# BUTTONS.net
KiCad netlist of a schematic drawn in Altium Designer
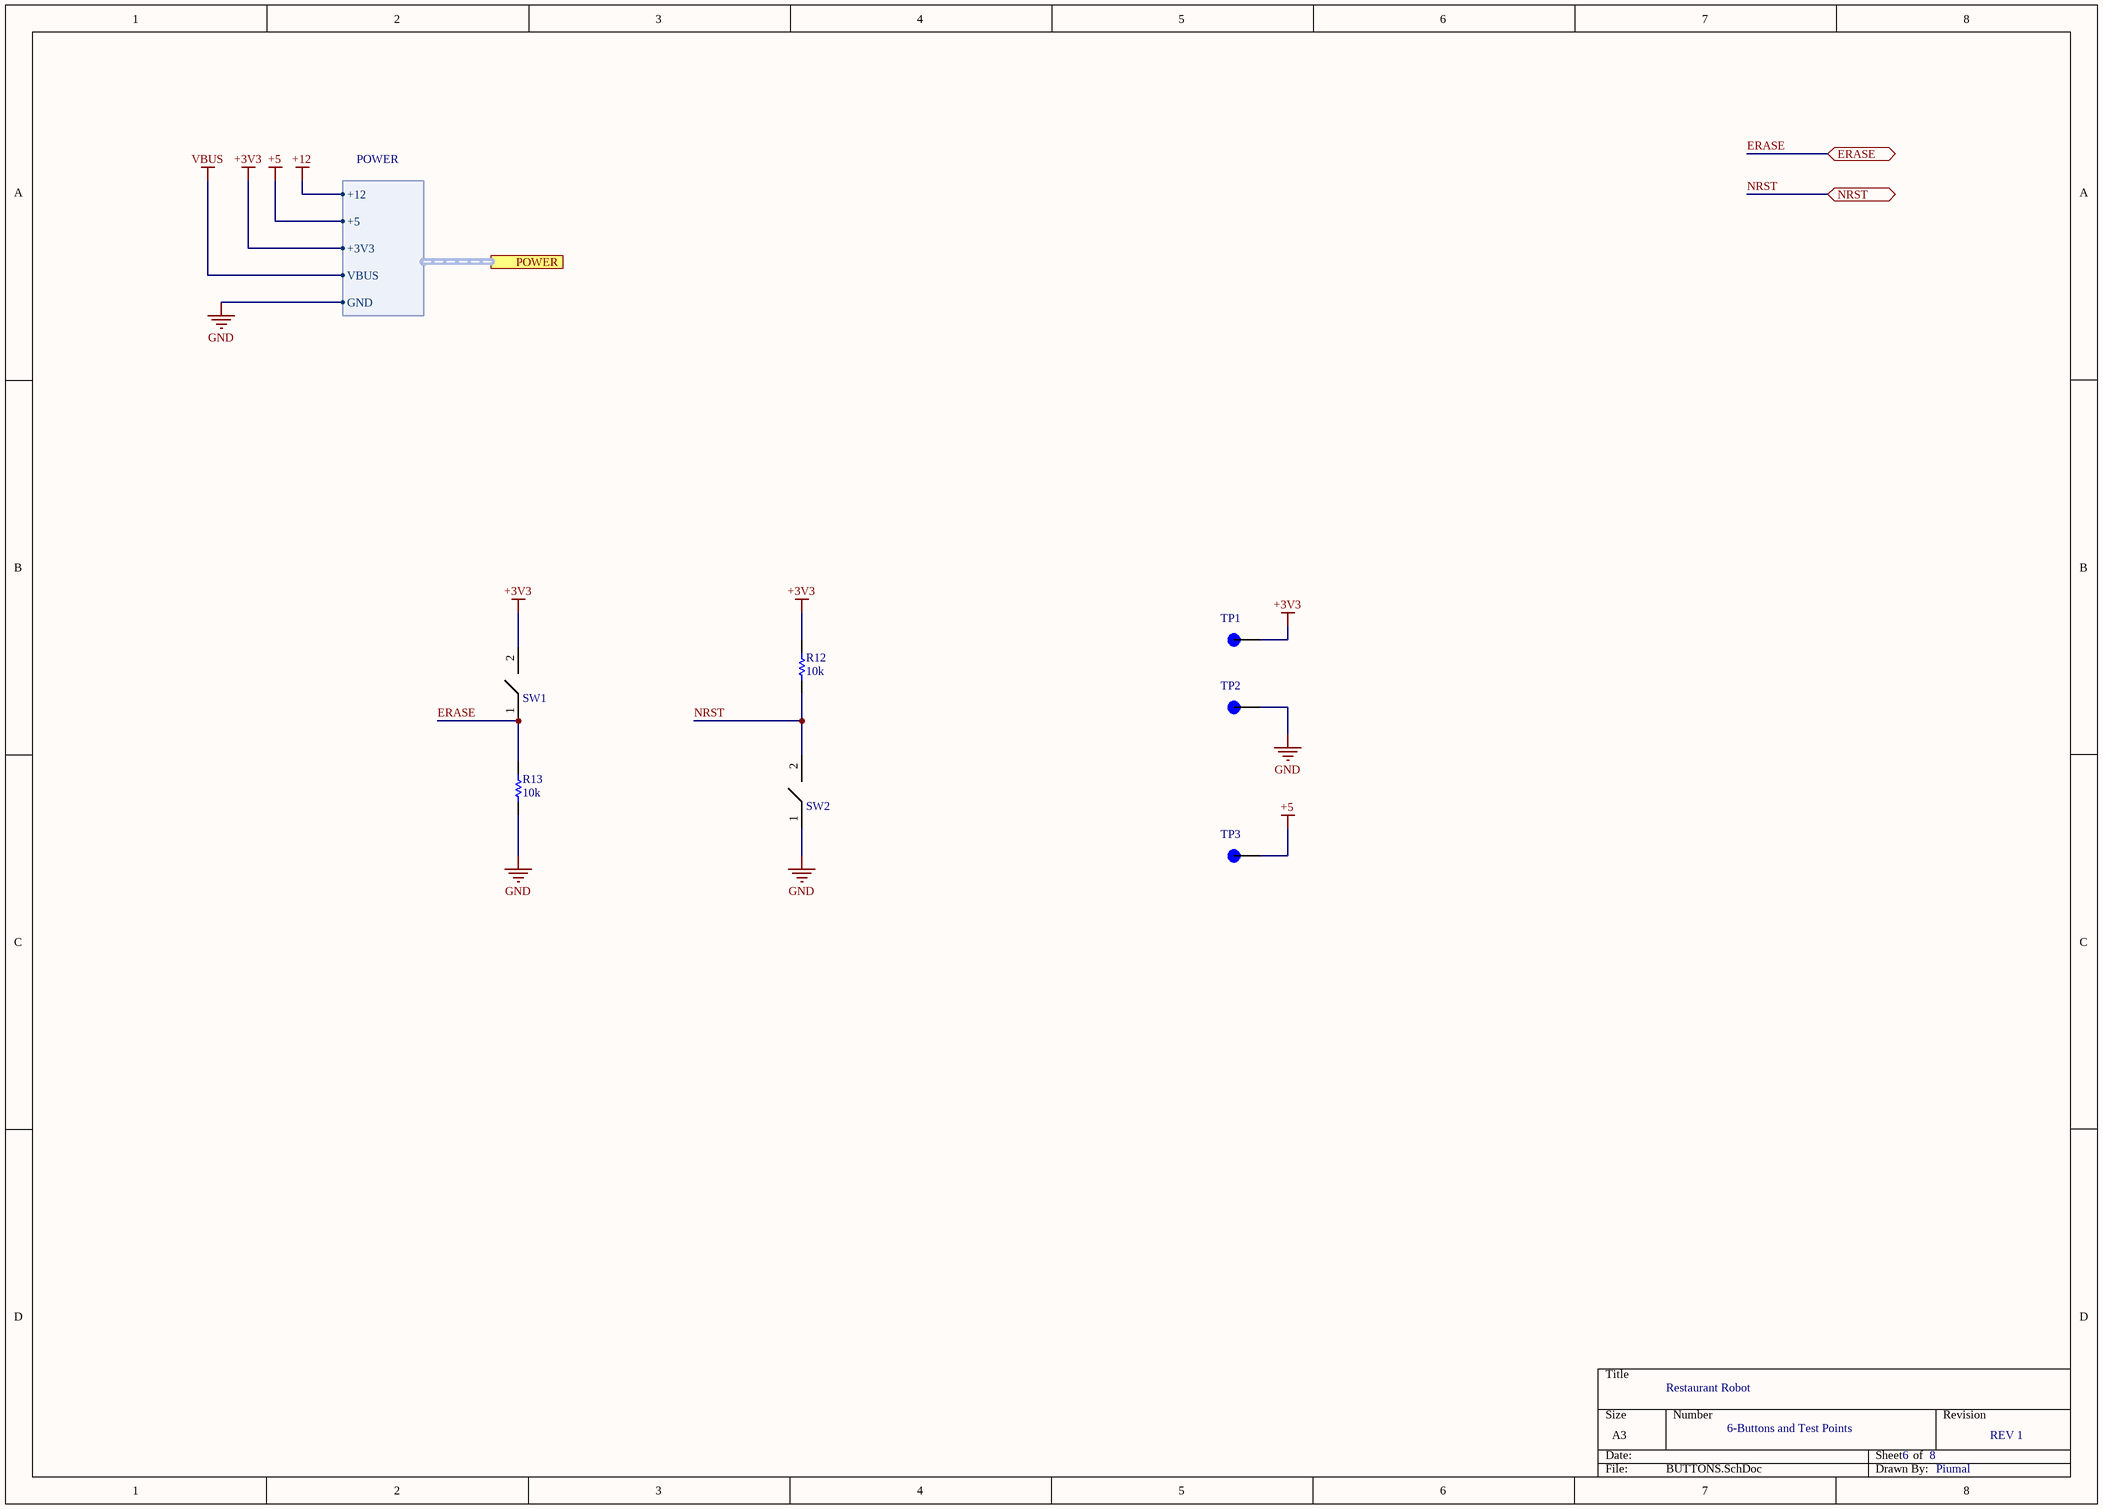
[diagram p0: BUTTONS.SchDoc]

(export (version "E")
  (design (tool "Eeschema 10.0.6"))
  (components
    (comp (ref "R12")
      (value "RC0805JR-0710KL")
      (footprint "RESC2013X60X35ML10T20")
      (description "Chip Resistor, 10 KOhm, +/- 5%, 0.125 W, -55 to 155 degC, 0805 (2012 Metric), RoHS, Tape and Reel")
      (fields (field (name "MANUFACTURER") "Yageo") (field (name "RESISTANCE") "10k"))
      (libsource (lib "Altium Content Vault") (part "RES-2"))
    )
    (comp (ref "R13")
      (value "RC0805JR-0710KL")
      (footprint "RESC2013X60X35ML10T20")
      (description "Chip Resistor, 10 KOhm, +/- 5%, 0.125 W, -55 to 155 degC, 0805 (2012 Metric), RoHS, Tape and Reel")
      (fields (field (name "MANUFACTURER") "Yageo") (field (name "RESISTANCE") "10k"))
      (libsource (lib "Altium Content Vault") (part "RES-2"))
    )
    (comp (ref "SW1")
      (value "SWITCH")
      (footprint "PCBComponent_1")
      (description "SWITCH TACTILE SPST-NO 0.05A 12V")
      (libsource (lib "TS-1011") (part "SW"))
    )
    (comp (ref "SW2")
      (value "SWITCH")
      (footprint "PCBComponent_1")
      (description "SWITCH TACTILE SPST-NO 0.05A 12V")
      (libsource (lib "TS-1011") (part "SW"))
    )
    (comp (ref "TP1")
      (value "5000")
      (footprint "KEYSTONE_5000")
      (fields (field (name "MF") "Keystone Electronics"))
      (libsource (lib "5000") (part "5000"))
    )
    (comp (ref "TP2")
      (value "5000")
      (footprint "KEYSTONE_5000")
      (fields (field (name "MF") "Keystone Electronics"))
      (libsource (lib "5000") (part "5000"))
    )
    (comp (ref "TP3")
      (value "5000")
      (footprint "KEYSTONE_5000")
      (fields (field (name "MF") "Keystone Electronics"))
      (libsource (lib "5000") (part "5000"))
    )
  )
  (nets
    (net (code "2") (name "+3V3") (class "Default")
      (node (ref "R12") (pin "2") (pinfunction "2_2") (pintype "passive"))
      (node (ref "SW1") (pin "2") (pinfunction "2_2") (pintype "passive"))
      (node (ref "TP1") (pin "TP") (pinfunction "TP_TP") (pintype "passive"))
    )
    (net (code "3") (name "+5") (class "Default")
      (node (ref "TP3") (pin "TP") (pinfunction "TP_TP") (pintype "passive"))
    )
    (net (code "5") (name "/ERASE") (class "Default")
      (node (ref "R13") (pin "2") (pinfunction "2_2") (pintype "passive"))
      (node (ref "SW1") (pin "1") (pinfunction "1_1") (pintype "passive"))
    )
    (net (code "6") (name "/NRST") (class "Default")
      (node (ref "R12") (pin "1") (pinfunction "1_1") (pintype "passive"))
      (node (ref "SW2") (pin "2") (pinfunction "2_2") (pintype "passive"))
    )
    (net (code "8") (name "GND") (class "Default")
      (node (ref "R13") (pin "1") (pinfunction "1_1") (pintype "passive"))
      (node (ref "SW2") (pin "1") (pinfunction "1_1") (pintype "passive"))
      (node (ref "TP2") (pin "TP") (pinfunction "TP_TP") (pintype "passive"))
    )
  )
)
